# TAH_BOARD_VER_2_0.net
KiCad netlist of a schematic drawn in EAGLE
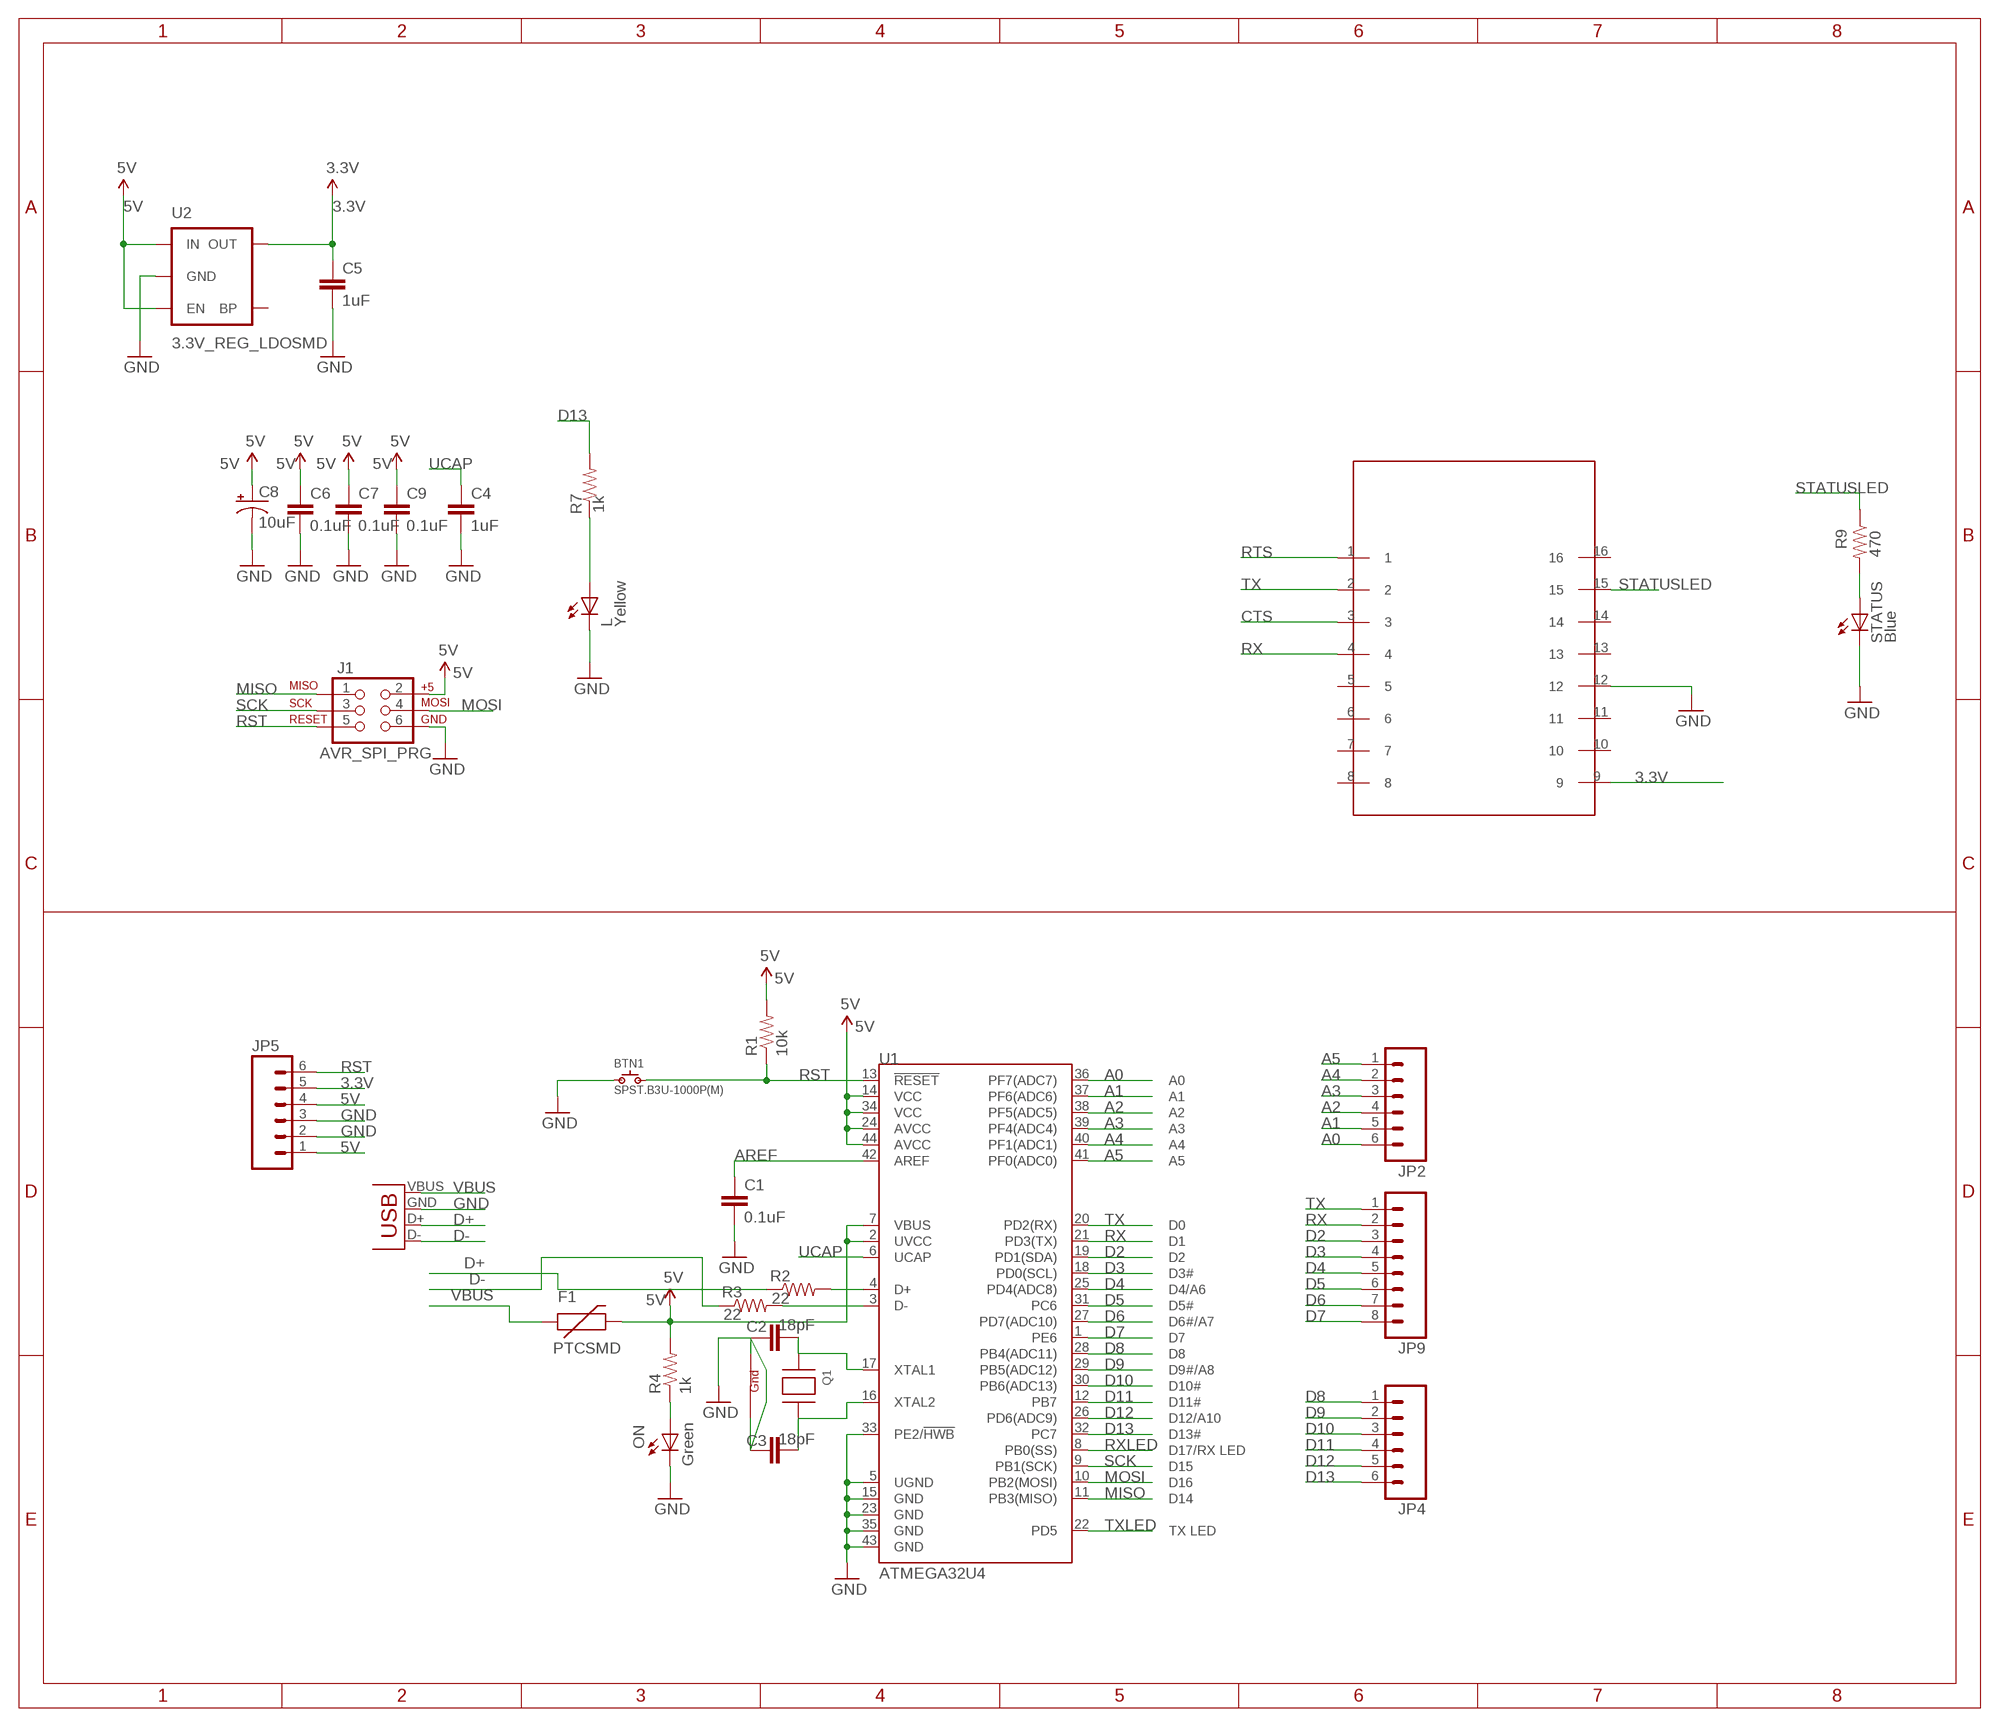
[diagram p0: schematic, sheet 1]

(export (version "E")
  (design (tool "Eeschema 10.0.6"))
  (components
    (comp (ref "BLE")
      (value "HM-11HM11")
      (footprint "eagle-import:BC05B-SMD")
      (libsource (lib "eagle-import") (part "HM-11HM11"))
    )
    (comp (ref "BTN1")
      (value "SPST.B3U-1000P(M)")
      (footprint "eagle-import:B3U-1000P(M)")
      (libsource (lib "eagle-import") (part "SPST.B3U-1000P(M)"))
    )
    (comp (ref "C1")
      (value "0.1uF")
      (footprint "eagle-import:1206")
      (libsource (lib "eagle-import") (part "2.2UF-CERCAP-10009"))
    )
    (comp (ref "C2")
      (value "18pF")
      (footprint "eagle-import:1206")
      (libsource (lib "eagle-import") (part "2.2UF-CERCAP-10009"))
    )
    (comp (ref "C3")
      (value "18pF")
      (footprint "eagle-import:1206")
      (libsource (lib "eagle-import") (part "2.2UF-CERCAP-10009"))
    )
    (comp (ref "C4")
      (value "1uF")
      (footprint "eagle-import:1206")
      (libsource (lib "eagle-import") (part "2.2UF-CERCAP-10009"))
    )
    (comp (ref "C5")
      (value "1uF")
      (footprint "eagle-import:1206")
      (libsource (lib "eagle-import") (part "2.2UF-CERCAP-10009"))
    )
    (comp (ref "C6")
      (value "0.1uF")
      (footprint "eagle-import:1206")
      (libsource (lib "eagle-import") (part "2.2UF-CERCAP-10009"))
    )
    (comp (ref "C7")
      (value "0.1uF")
      (footprint "eagle-import:1206")
      (libsource (lib "eagle-import") (part "2.2UF-CERCAP-10009"))
    )
    (comp (ref "C8")
      (value "10uF")
      (footprint "eagle-import:EIA3216")
      (libsource (lib "eagle-import") (part "CAP_POL1206"))
    )
    (comp (ref "C9")
      (value "0.1uF")
      (footprint "eagle-import:1206")
      (libsource (lib "eagle-import") (part "2.2UF-CERCAP-10009"))
    )
    (comp (ref "F1")
      (value "PTCSMD")
      (footprint "eagle-import:PTC-1206")
      (libsource (lib "eagle-import") (part "PTCSMD"))
    )
    (comp (ref "J1")
      (value "AVR_SPI_PRG")
      (footprint "eagle-import:2X3")
      (libsource (lib "eagle-import") (part "AVR_SPI_PRG_6PTH"))
    )
    (comp (ref "JP2")
      (value "M06SIP")
      (footprint "eagle-import:1X06")
      (libsource (lib "eagle-import") (part "M06SIP"))
    )
    (comp (ref "JP4")
      (value "M06SIP")
      (footprint "eagle-import:1X06")
      (libsource (lib "eagle-import") (part "M06SIP"))
    )
    (comp (ref "JP5")
      (value "M06SIP")
      (footprint "eagle-import:1X06")
      (libsource (lib "eagle-import") (part "M06SIP"))
    )
    (comp (ref "JP7")
      (value "USB-A-H")
      (footprint "eagle-import:USB-A-H")
      (libsource (lib "eagle-import") (part "USB-A-H"))
    )
    (comp (ref "JP9")
      (value "M081X08")
      (footprint "eagle-import:1X08")
      (libsource (lib "eagle-import") (part "M081X08"))
    )
    (comp (ref "L")
      (value "Yellow")
      (footprint "eagle-import:1206")
      (libsource (lib "eagle-import") (part "LEDSMT1206"))
    )
    (comp (ref "ON")
      (value "Green")
      (footprint "eagle-import:1206")
      (libsource (lib "eagle-import") (part "LEDSMT1206"))
    )
    (comp (ref "Q1")
      (value "XTAL-4-3225")
      (footprint "eagle-import:NX3225")
      (libsource (lib "eagle-import") (part "XTAL-4-3225"))
    )
    (comp (ref "R1")
      (value "10k")
      (footprint "eagle-import:1206")
      (libsource (lib "eagle-import") (part "RESISTOR1206"))
    )
    (comp (ref "R2")
      (value "22")
      (footprint "eagle-import:1206")
      (libsource (lib "eagle-import") (part "RESISTOR1206"))
    )
    (comp (ref "R3")
      (value "22")
      (footprint "eagle-import:1206")
      (libsource (lib "eagle-import") (part "RESISTOR1206"))
    )
    (comp (ref "R4")
      (value "1k")
      (footprint "eagle-import:1206")
      (libsource (lib "eagle-import") (part "RESISTOR1206"))
    )
    (comp (ref "R7")
      (value "1k")
      (footprint "eagle-import:1206")
      (libsource (lib "eagle-import") (part "RESISTOR1206"))
    )
    (comp (ref "R9")
      (value "470")
      (footprint "eagle-import:1206")
      (libsource (lib "eagle-import") (part "RESISTOR1206"))
    )
    (comp (ref "STATUS")
      (value "Blue")
      (footprint "eagle-import:1206")
      (libsource (lib "eagle-import") (part "LEDSMT1206"))
    )
    (comp (ref "U1")
      (value "ATMEGA32U4")
      (footprint "eagle-import:SPARKFUN-DIGITALIC_TQFP44")
      (libsource (lib "eagle-import") (part "ATMEGA32U4TQFP"))
    )
    (comp (ref "U2")
      (value "3.3V_REG_LDOSMD")
      (footprint "eagle-import:SOT23-5")
      (libsource (lib "eagle-import") (part "V_REG_LDOSMD"))
    )
  )
  (nets
    (net (code "1") (name "/A0") (class "Default")
      (node (ref "JP2") (pin "6") (pinfunction "6_6") (pintype "passive"))
      (node (ref "U1") (pin "36") (pinfunction "PF7(ADC7)_36") (pintype "bidirectional"))
    )
    (net (code "2") (name "/A1") (class "Default")
      (node (ref "JP2") (pin "5") (pinfunction "5_5") (pintype "passive"))
      (node (ref "U1") (pin "37") (pinfunction "PF6(ADC6)_37") (pintype "bidirectional"))
    )
    (net (code "3") (name "/A2") (class "Default")
      (node (ref "JP2") (pin "4") (pinfunction "4_4") (pintype "passive"))
      (node (ref "U1") (pin "38") (pinfunction "PF5(ADC5)_38") (pintype "bidirectional"))
    )
    (net (code "4") (name "/A3") (class "Default")
      (node (ref "JP2") (pin "3") (pinfunction "3_3") (pintype "passive"))
      (node (ref "U1") (pin "39") (pinfunction "PF4(ADC4)_39") (pintype "bidirectional"))
    )
    (net (code "5") (name "/A4") (class "Default")
      (node (ref "JP2") (pin "2") (pinfunction "2_2") (pintype "passive"))
      (node (ref "U1") (pin "40") (pinfunction "PF1(ADC1)_40") (pintype "bidirectional"))
    )
    (net (code "6") (name "/A5") (class "Default")
      (node (ref "JP2") (pin "1") (pinfunction "1_1") (pintype "passive"))
      (node (ref "U1") (pin "41") (pinfunction "PF0(ADC0)_41") (pintype "bidirectional"))
    )
    (net (code "7") (name "/AREF") (class "Default")
      (node (ref "C1") (pin "1") (pinfunction "1_1") (pintype "passive"))
      (node (ref "U1") (pin "42") (pinfunction "AREF_42") (pintype "bidirectional"))
    )
    (net (code "8") (name "/CTS") (class "Default")
      (node (ref "BLE") (pin "3") (pinfunction "3_3") (pintype "bidirectional"))
    )
    (net (code "9") (name "/D+") (class "Default")
      (node (ref "JP7") (pin "D+") (pinfunction "D-_D+") (pintype "bidirectional"))
      (node (ref "R2") (pin "1") (pinfunction "1_1") (pintype "passive"))
    )
    (net (code "10") (name "/D-") (class "Default")
      (node (ref "JP7") (pin "D-") (pinfunction "D+_D-") (pintype "bidirectional"))
      (node (ref "R3") (pin "1") (pinfunction "1_1") (pintype "passive"))
    )
    (net (code "11") (name "/D2") (class "Default")
      (node (ref "JP9") (pin "3") (pinfunction "3_3") (pintype "passive"))
      (node (ref "U1") (pin "19") (pinfunction "PD1(SDA)_19") (pintype "bidirectional"))
    )
    (net (code "12") (name "/D3") (class "Default")
      (node (ref "JP9") (pin "4") (pinfunction "4_4") (pintype "passive"))
      (node (ref "U1") (pin "18") (pinfunction "PD0(SCL)_18") (pintype "bidirectional"))
    )
    (net (code "13") (name "/D4") (class "Default")
      (node (ref "JP9") (pin "5") (pinfunction "5_5") (pintype "passive"))
      (node (ref "U1") (pin "25") (pinfunction "PD4(ADC8)_25") (pintype "bidirectional"))
    )
    (net (code "14") (name "/D5") (class "Default")
      (node (ref "JP9") (pin "6") (pinfunction "6_6") (pintype "passive"))
      (node (ref "U1") (pin "31") (pinfunction "PC6_31") (pintype "bidirectional"))
    )
    (net (code "15") (name "/D6") (class "Default")
      (node (ref "JP9") (pin "7") (pinfunction "7_7") (pintype "passive"))
      (node (ref "U1") (pin "27") (pinfunction "PD7(ADC10)_27") (pintype "bidirectional"))
    )
    (net (code "16") (name "/D7") (class "Default")
      (node (ref "JP9") (pin "8") (pinfunction "8_8") (pintype "passive"))
      (node (ref "U1") (pin "1") (pinfunction "PE6_1") (pintype "bidirectional"))
    )
    (net (code "17") (name "/D8") (class "Default")
      (node (ref "JP4") (pin "1") (pinfunction "1_1") (pintype "passive"))
      (node (ref "U1") (pin "28") (pinfunction "PB4(ADC11)_28") (pintype "bidirectional"))
    )
    (net (code "18") (name "/D9") (class "Default")
      (node (ref "JP4") (pin "2") (pinfunction "2_2") (pintype "passive"))
      (node (ref "U1") (pin "29") (pinfunction "PB5(ADC12)_29") (pintype "bidirectional"))
    )
    (net (code "19") (name "/D10") (class "Default")
      (node (ref "JP4") (pin "3") (pinfunction "3_3") (pintype "passive"))
      (node (ref "U1") (pin "30") (pinfunction "PB6(ADC13)_30") (pintype "bidirectional"))
    )
    (net (code "20") (name "/D11") (class "Default")
      (node (ref "JP4") (pin "4") (pinfunction "4_4") (pintype "passive"))
      (node (ref "U1") (pin "12") (pinfunction "PB7_12") (pintype "bidirectional"))
    )
    (net (code "21") (name "/D12") (class "Default")
      (node (ref "JP4") (pin "5") (pinfunction "5_5") (pintype "passive"))
      (node (ref "U1") (pin "26") (pinfunction "PD6(ADC9)_26") (pintype "bidirectional"))
    )
    (net (code "22") (name "/D13") (class "Default")
      (node (ref "JP4") (pin "6") (pinfunction "6_6") (pintype "passive"))
      (node (ref "R7") (pin "2") (pinfunction "2_2") (pintype "passive"))
      (node (ref "U1") (pin "32") (pinfunction "PC7_32") (pintype "bidirectional"))
    )
    (net (code "23") (name "/MISO") (class "Default")
      (node (ref "J1") (pin "1") (pinfunction "1_1") (pintype "passive"))
      (node (ref "U1") (pin "11") (pinfunction "PB3(MISO)_11") (pintype "bidirectional"))
    )
    (net (code "24") (name "/MOSI") (class "Default")
      (node (ref "J1") (pin "4") (pinfunction "4_4") (pintype "passive"))
      (node (ref "U1") (pin "10") (pinfunction "PB2(MOSI)_10") (pintype "bidirectional"))
    )
    (net (code "25") (name "/RST") (class "Default")
      (node (ref "BTN1") (pin "2") (pinfunction "2_2") (pintype "bidirectional"))
      (node (ref "J1") (pin "5") (pinfunction "5_5") (pintype "passive"))
      (node (ref "JP5") (pin "6") (pinfunction "6_6") (pintype "passive"))
      (node (ref "R1") (pin "1") (pinfunction "1_1") (pintype "passive"))
      (node (ref "U1") (pin "13") (pinfunction "~{RESET}_13") (pintype "bidirectional"))
    )
    (net (code "26") (name "/RTS") (class "Default")
      (node (ref "BLE") (pin "1") (pinfunction "1_1") (pintype "bidirectional"))
    )
    (net (code "27") (name "/RX") (class "Default")
      (node (ref "BLE") (pin "4") (pinfunction "4_4") (pintype "bidirectional"))
      (node (ref "JP9") (pin "2") (pinfunction "2_2") (pintype "passive"))
      (node (ref "U1") (pin "21") (pinfunction "PD3(TX)_21") (pintype "bidirectional"))
    )
    (net (code "28") (name "/RXLED") (class "Default")
      (node (ref "U1") (pin "8") (pinfunction "PB0(SS)_8") (pintype "bidirectional"))
    )
    (net (code "29") (name "/SCK") (class "Default")
      (node (ref "J1") (pin "3") (pinfunction "3_3") (pintype "passive"))
      (node (ref "U1") (pin "9") (pinfunction "PB1(SCK)_9") (pintype "bidirectional"))
    )
    (net (code "30") (name "/STATUSLED") (class "Default")
      (node (ref "BLE") (pin "15") (pinfunction "15_15") (pintype "bidirectional"))
      (node (ref "R9") (pin "1") (pinfunction "1_1") (pintype "passive"))
    )
    (net (code "31") (name "/TX") (class "Default")
      (node (ref "BLE") (pin "2") (pinfunction "2_2") (pintype "bidirectional"))
      (node (ref "JP9") (pin "1") (pinfunction "1_1") (pintype "passive"))
      (node (ref "U1") (pin "20") (pinfunction "PD2(RX)_20") (pintype "bidirectional"))
    )
    (net (code "32") (name "/TXLED") (class "Default")
      (node (ref "U1") (pin "22") (pinfunction "PD5_22") (pintype "bidirectional"))
    )
    (net (code "33") (name "/UCAP") (class "Default")
      (node (ref "C4") (pin "1") (pinfunction "1_1") (pintype "passive"))
      (node (ref "U1") (pin "6") (pinfunction "UCAP_6") (pintype "bidirectional"))
    )
    (net (code "34") (name "/VBUS") (class "Default")
      (node (ref "F1") (pin "1") (pinfunction "1_1") (pintype "bidirectional"))
      (node (ref "JP7") (pin "VBUS") (pinfunction "GND_VBUS") (pintype "bidirectional"))
    )
    (net (code "35") (name "3.3V") (class "Default")
      (node (ref "BLE") (pin "9") (pinfunction "9_9") (pintype "bidirectional"))
      (node (ref "C5") (pin "1") (pinfunction "1_1") (pintype "passive"))
      (node (ref "JP5") (pin "5") (pinfunction "5_5") (pintype "passive"))
      (node (ref "U2") (pin "5") (pinfunction "OUT_5") (pintype "passive"))
    )
    (net (code "36") (name "5V") (class "Default")
      (node (ref "C6") (pin "1") (pinfunction "1_1") (pintype "passive"))
      (node (ref "C7") (pin "1") (pinfunction "1_1") (pintype "passive"))
      (node (ref "C8") (pin "A") (pinfunction "+_A") (pintype "passive"))
      (node (ref "C9") (pin "1") (pinfunction "1_1") (pintype "passive"))
      (node (ref "F1") (pin "2") (pinfunction "2_2") (pintype "bidirectional"))
      (node (ref "J1") (pin "2") (pinfunction "2_2") (pintype "passive"))
      (node (ref "JP5") (pin "1") (pinfunction "1_1") (pintype "passive"))
      (node (ref "JP5") (pin "4") (pinfunction "4_4") (pintype "passive"))
      (node (ref "R1") (pin "2") (pinfunction "2_2") (pintype "passive"))
      (node (ref "R4") (pin "2") (pinfunction "2_2") (pintype "passive"))
      (node (ref "U1") (pin "14") (pinfunction "VCC_14") (pintype "bidirectional"))
      (node (ref "U1") (pin "2") (pinfunction "UVCC_2") (pintype "bidirectional"))
      (node (ref "U1") (pin "24") (pinfunction "AVCC_24") (pintype "bidirectional"))
      (node (ref "U1") (pin "34") (pinfunction "VCC_34") (pintype "bidirectional"))
      (node (ref "U1") (pin "44") (pinfunction "AVCC_44") (pintype "bidirectional"))
      (node (ref "U1") (pin "7") (pinfunction "VBUS_7") (pintype "bidirectional"))
      (node (ref "U2") (pin "1") (pinfunction "IN_1") (pintype "input"))
      (node (ref "U2") (pin "3") (pinfunction "EN_3") (pintype "input"))
    )
    (net (code "37") (name "GND") (class "Default")
      (node (ref "BLE") (pin "12") (pinfunction "12_12") (pintype "bidirectional"))
      (node (ref "BTN1") (pin "1") (pinfunction "1_1") (pintype "bidirectional"))
      (node (ref "C1") (pin "2") (pinfunction "2_2") (pintype "passive"))
      (node (ref "C2") (pin "1") (pinfunction "1_1") (pintype "passive"))
      (node (ref "C3") (pin "1") (pinfunction "1_1") (pintype "passive"))
      (node (ref "C4") (pin "2") (pinfunction "2_2") (pintype "passive"))
      (node (ref "C5") (pin "2") (pinfunction "2_2") (pintype "passive"))
      (node (ref "C6") (pin "2") (pinfunction "2_2") (pintype "passive"))
      (node (ref "C7") (pin "2") (pinfunction "2_2") (pintype "passive"))
      (node (ref "C8") (pin "C") (pinfunction "-_C") (pintype "passive"))
      (node (ref "C9") (pin "2") (pinfunction "2_2") (pintype "passive"))
      (node (ref "J1") (pin "6") (pinfunction "6_6") (pintype "passive"))
      (node (ref "JP5") (pin "2") (pinfunction "2_2") (pintype "passive"))
      (node (ref "JP5") (pin "3") (pinfunction "3_3") (pintype "passive"))
      (node (ref "JP7") (pin "GND") (pinfunction "VBUS_GND") (pintype "bidirectional"))
      (node (ref "L") (pin "C") (pinfunction "C_C") (pintype "passive"))
      (node (ref "ON") (pin "C") (pinfunction "C_C") (pintype "passive"))
      (node (ref "Q1") (pin "2") (pinfunction "G2_2") (pintype "power_in"))
      (node (ref "Q1") (pin "4") (pinfunction "G1_4") (pintype "power_in"))
      (node (ref "STATUS") (pin "C") (pinfunction "C_C") (pintype "passive"))
      (node (ref "U1") (pin "15") (pinfunction "GND_15") (pintype "bidirectional"))
      (node (ref "U1") (pin "23") (pinfunction "GND_23") (pintype "bidirectional"))
      (node (ref "U1") (pin "33") (pinfunction "PE2/~{HWB}_33") (pintype "bidirectional"))
      (node (ref "U1") (pin "35") (pinfunction "GND_35") (pintype "bidirectional"))
      (node (ref "U1") (pin "43") (pinfunction "GND_43") (pintype "bidirectional"))
      (node (ref "U1") (pin "5") (pinfunction "UGND_5") (pintype "bidirectional"))
      (node (ref "U2") (pin "2") (pinfunction "GND_2") (pintype "input"))
    )
    (net (code "38") (name "Net-(L-PadA)") (class "Default")
      (node (ref "L") (pin "A") (pinfunction "A_A") (pintype "passive"))
      (node (ref "R7") (pin "1") (pinfunction "1_1") (pintype "passive"))
    )
    (net (code "39") (name "Net-(ON-PadA)") (class "Default")
      (node (ref "ON") (pin "A") (pinfunction "A_A") (pintype "passive"))
      (node (ref "R4") (pin "1") (pinfunction "1_1") (pintype "passive"))
    )
    (net (code "40") (name "Net-(Q1-X1)") (class "Default")
      (node (ref "C2") (pin "2") (pinfunction "2_2") (pintype "passive"))
      (node (ref "Q1") (pin "1") (pinfunction "X1_1") (pintype "bidirectional"))
      (node (ref "U1") (pin "17") (pinfunction "XTAL1_17") (pintype "bidirectional"))
    )
    (net (code "41") (name "Net-(Q1-X2)") (class "Default")
      (node (ref "C3") (pin "2") (pinfunction "2_2") (pintype "passive"))
      (node (ref "Q1") (pin "3") (pinfunction "X2_3") (pintype "bidirectional"))
      (node (ref "U1") (pin "16") (pinfunction "XTAL2_16") (pintype "bidirectional"))
    )
    (net (code "42") (name "Net-(R9-Pad2)") (class "Default")
      (node (ref "R9") (pin "2") (pinfunction "2_2") (pintype "passive"))
      (node (ref "STATUS") (pin "A") (pinfunction "A_A") (pintype "passive"))
    )
    (net (code "43") (name "Net-(U1-D+)") (class "Default")
      (node (ref "R2") (pin "2") (pinfunction "2_2") (pintype "passive"))
      (node (ref "U1") (pin "4") (pinfunction "D+_4") (pintype "bidirectional"))
    )
    (net (code "44") (name "Net-(U1-D-)") (class "Default")
      (node (ref "R3") (pin "2") (pinfunction "2_2") (pintype "passive"))
      (node (ref "U1") (pin "3") (pinfunction "D-_3") (pintype "bidirectional"))
    )
    (net (code "45") (name "unconnected-(BLE-Pad5)") (class "Default")
      (node (ref "BLE") (pin "5") (pinfunction "5_5") (pintype "bidirectional"))
    )
    (net (code "46") (name "unconnected-(BLE-Pad6)") (class "Default")
      (node (ref "BLE") (pin "6") (pinfunction "6_6") (pintype "bidirectional"))
    )
    (net (code "47") (name "unconnected-(BLE-Pad7)") (class "Default")
      (node (ref "BLE") (pin "7") (pinfunction "7_7") (pintype "bidirectional"))
    )
    (net (code "48") (name "unconnected-(BLE-Pad8)") (class "Default")
      (node (ref "BLE") (pin "8") (pinfunction "8_8") (pintype "bidirectional"))
    )
    (net (code "49") (name "unconnected-(BLE-Pad10)") (class "Default")
      (node (ref "BLE") (pin "10") (pinfunction "10_10") (pintype "bidirectional"))
    )
    (net (code "50") (name "unconnected-(BLE-Pad11)") (class "Default")
      (node (ref "BLE") (pin "11") (pinfunction "11_11") (pintype "bidirectional"))
    )
    (net (code "51") (name "unconnected-(BLE-Pad13)") (class "Default")
      (node (ref "BLE") (pin "13") (pinfunction "13_13") (pintype "bidirectional"))
    )
    (net (code "52") (name "unconnected-(BLE-Pad14)") (class "Default")
      (node (ref "BLE") (pin "14") (pinfunction "14_14") (pintype "bidirectional"))
    )
    (net (code "53") (name "unconnected-(BLE-Pad16)") (class "Default")
      (node (ref "BLE") (pin "16") (pinfunction "16_16") (pintype "bidirectional"))
    )
    (net (code "54") (name "unconnected-(U2-BP-Pad4)") (class "Default")
      (node (ref "U2") (pin "4") (pinfunction "BP_4") (pintype "input"))
    )
  )
)
